# MainHubPCB.net
KiCad netlist of a schematic drawn in EAGLE
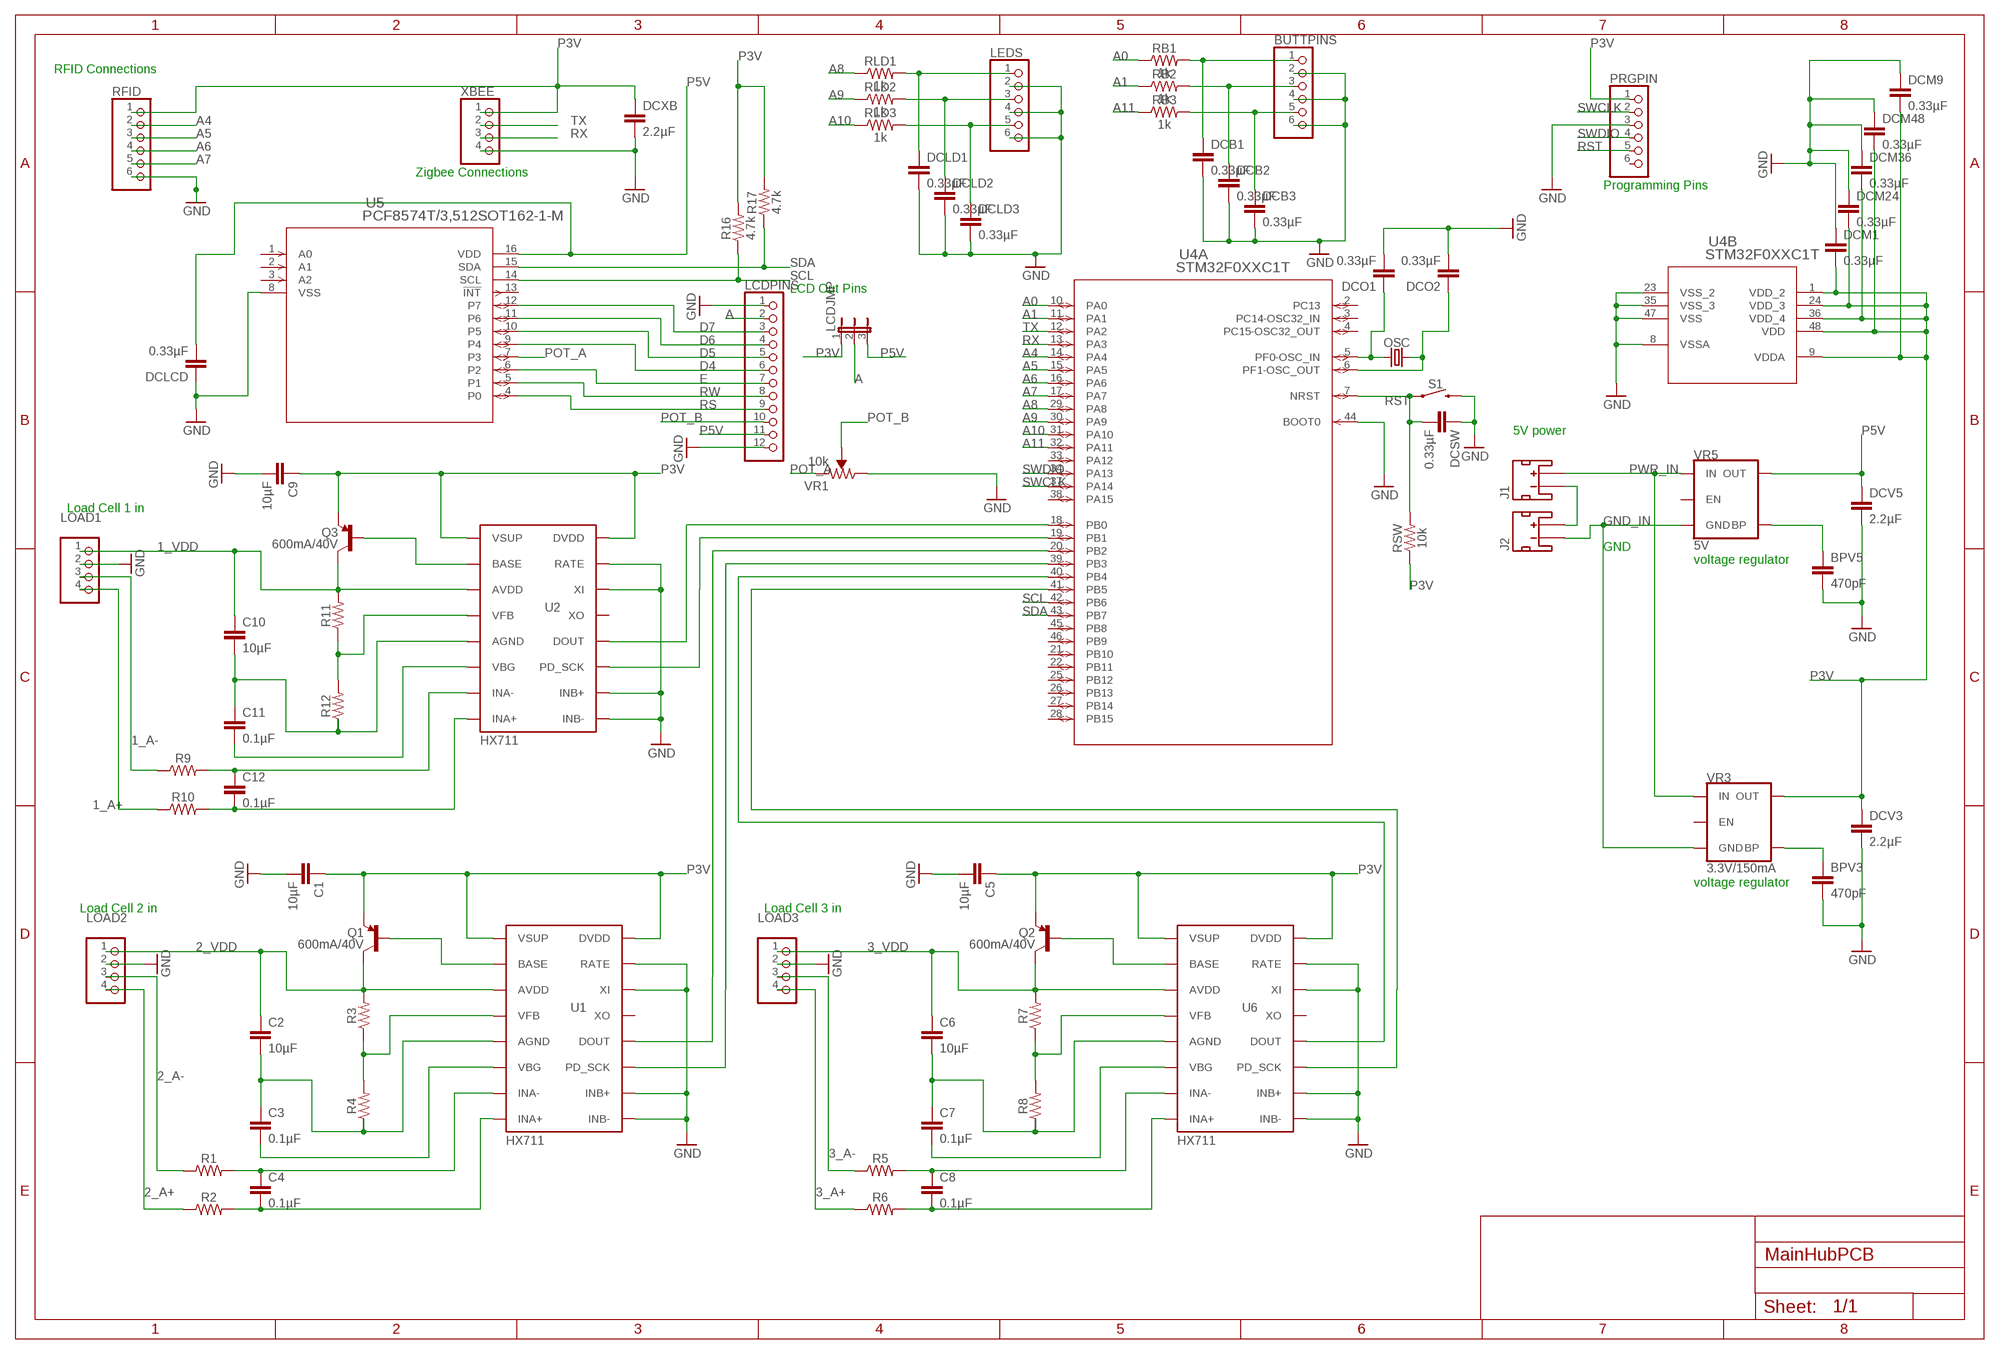
[diagram p0: schematic, sheet 1]

(export (version "E")
  (design (tool "Eeschema 10.0.6"))
  (components
    (comp (ref "BPV3")
      (value "470pF")
      (footprint "eagle-import:0805")
      (libsource (lib "eagle-import") (part "0.33UF/330NF-0805-50V-10%"))
    )
    (comp (ref "BPV5")
      (value "470pF")
      (footprint "eagle-import:0805")
      (libsource (lib "eagle-import") (part "0.33UF/330NF-0805-50V-10%"))
    )
    (comp (ref "BUTTPINS")
      (value "PINHD-1X6")
      (footprint "eagle-import:1X06")
      (libsource (lib "eagle-import") (part "PINHD-1X6"))
    )
    (comp (ref "C1")
      (value "10µF")
      (footprint "eagle-import:0805")
      (libsource (lib "eagle-import") (part "0.33UF/330NF-0805-50V-10%"))
    )
    (comp (ref "C2")
      (value "10µF")
      (footprint "eagle-import:0805")
      (libsource (lib "eagle-import") (part "0.33UF/330NF-0805-50V-10%"))
    )
    (comp (ref "C3")
      (value "0.1µF")
      (footprint "eagle-import:0805")
      (libsource (lib "eagle-import") (part "0.33UF/330NF-0805-50V-10%"))
    )
    (comp (ref "C4")
      (value "0.1µF")
      (footprint "eagle-import:0805")
      (libsource (lib "eagle-import") (part "0.33UF/330NF-0805-50V-10%"))
    )
    (comp (ref "C5")
      (value "10µF")
      (footprint "eagle-import:0805")
      (libsource (lib "eagle-import") (part "0.33UF/330NF-0805-50V-10%"))
    )
    (comp (ref "C6")
      (value "10µF")
      (footprint "eagle-import:0805")
      (libsource (lib "eagle-import") (part "0.33UF/330NF-0805-50V-10%"))
    )
    (comp (ref "C7")
      (value "0.1µF")
      (footprint "eagle-import:0805")
      (libsource (lib "eagle-import") (part "0.33UF/330NF-0805-50V-10%"))
    )
    (comp (ref "C8")
      (value "0.1µF")
      (footprint "eagle-import:0805")
      (libsource (lib "eagle-import") (part "0.33UF/330NF-0805-50V-10%"))
    )
    (comp (ref "C9")
      (value "10µF")
      (footprint "eagle-import:0805")
      (libsource (lib "eagle-import") (part "0.33UF/330NF-0805-50V-10%"))
    )
    (comp (ref "C10")
      (value "10µF")
      (footprint "eagle-import:0805")
      (libsource (lib "eagle-import") (part "0.33UF/330NF-0805-50V-10%"))
    )
    (comp (ref "C11")
      (value "0.1µF")
      (footprint "eagle-import:0805")
      (libsource (lib "eagle-import") (part "0.33UF/330NF-0805-50V-10%"))
    )
    (comp (ref "C12")
      (value "0.1µF")
      (footprint "eagle-import:0805")
      (libsource (lib "eagle-import") (part "0.33UF/330NF-0805-50V-10%"))
    )
    (comp (ref "DCB1")
      (value "0.33µF")
      (footprint "eagle-import:0805")
      (libsource (lib "eagle-import") (part "0.33UF/330NF-0805-50V-10%"))
    )
    (comp (ref "DCB2")
      (value "0.33µF")
      (footprint "eagle-import:0805")
      (libsource (lib "eagle-import") (part "0.33UF/330NF-0805-50V-10%"))
    )
    (comp (ref "DCB3")
      (value "0.33µF")
      (footprint "eagle-import:0805")
      (libsource (lib "eagle-import") (part "0.33UF/330NF-0805-50V-10%"))
    )
    (comp (ref "DCLCD")
      (value "0.33µF")
      (footprint "eagle-import:0805")
      (libsource (lib "eagle-import") (part "0.33UF/330NF-0805-50V-10%"))
    )
    (comp (ref "DCLD1")
      (value "0.33µF")
      (footprint "eagle-import:0805")
      (libsource (lib "eagle-import") (part "0.33UF/330NF-0805-50V-10%"))
    )
    (comp (ref "DCLD2")
      (value "0.33µF")
      (footprint "eagle-import:0805")
      (libsource (lib "eagle-import") (part "0.33UF/330NF-0805-50V-10%"))
    )
    (comp (ref "DCLD3")
      (value "0.33µF")
      (footprint "eagle-import:0805")
      (libsource (lib "eagle-import") (part "0.33UF/330NF-0805-50V-10%"))
    )
    (comp (ref "DCM1")
      (value "0.33µF")
      (footprint "eagle-import:0805")
      (libsource (lib "eagle-import") (part "0.33UF/330NF-0805-50V-10%"))
    )
    (comp (ref "DCM9")
      (value "0.33µF")
      (footprint "eagle-import:0805")
      (libsource (lib "eagle-import") (part "0.33UF/330NF-0805-50V-10%"))
    )
    (comp (ref "DCM24")
      (value "0.33µF")
      (footprint "eagle-import:0805")
      (libsource (lib "eagle-import") (part "0.33UF/330NF-0805-50V-10%"))
    )
    (comp (ref "DCM36")
      (value "0.33µF")
      (footprint "eagle-import:0805")
      (libsource (lib "eagle-import") (part "0.33UF/330NF-0805-50V-10%"))
    )
    (comp (ref "DCM48")
      (value "0.33µF")
      (footprint "eagle-import:0805")
      (libsource (lib "eagle-import") (part "0.33UF/330NF-0805-50V-10%"))
    )
    (comp (ref "DCO1")
      (value "0.33µF")
      (footprint "eagle-import:0805")
      (libsource (lib "eagle-import") (part "0.33UF/330NF-0805-50V-10%"))
    )
    (comp (ref "DCO2")
      (value "0.33µF")
      (footprint "eagle-import:0805")
      (libsource (lib "eagle-import") (part "0.33UF/330NF-0805-50V-10%"))
    )
    (comp (ref "DCSW")
      (value "0.33µF")
      (footprint "eagle-import:0805")
      (libsource (lib "eagle-import") (part "0.33UF/330NF-0805-50V-10%"))
    )
    (comp (ref "DCV3")
      (value "2.2µF")
      (footprint "eagle-import:0805")
      (libsource (lib "eagle-import") (part "0.33UF/330NF-0805-50V-10%"))
    )
    (comp (ref "DCV5")
      (value "2.2µF")
      (footprint "eagle-import:0805")
      (libsource (lib "eagle-import") (part "0.33UF/330NF-0805-50V-10%"))
    )
    (comp (ref "DCXB")
      (value "2.2µF")
      (footprint "eagle-import:0805")
      (libsource (lib "eagle-import") (part "0.33UF/330NF-0805-50V-10%"))
    )
    (comp (ref "J1")
      (value "JST_2MM_MALE")
      (footprint "eagle-import:JST-2-SMD")
      (libsource (lib "eagle-import") (part "JST_2MM_MALE"))
    )
    (comp (ref "J2")
      (value "JST_2MM_MALE")
      (footprint "eagle-import:JST-2-SMD")
      (libsource (lib "eagle-import") (part "JST_2MM_MALE"))
    )
    (comp (ref "LCDJMP")
      (value "JP2E")
      (footprint "eagle-import:JP2")
      (libsource (lib "eagle-import") (part "JP2E"))
    )
    (comp (ref "LCDPINS")
      (value "PINHD-1X12")
      (footprint "eagle-import:1X12")
      (libsource (lib "eagle-import") (part "PINHD-1X12"))
    )
    (comp (ref "LEDS")
      (value "PINHD-1X6")
      (footprint "eagle-import:1X06")
      (libsource (lib "eagle-import") (part "PINHD-1X6"))
    )
    (comp (ref "LOAD1")
      (value "PINHD-1X4")
      (footprint "eagle-import:1X04")
      (libsource (lib "eagle-import") (part "PINHD-1X4"))
    )
    (comp (ref "LOAD2")
      (value "PINHD-1X4")
      (footprint "eagle-import:1X04")
      (libsource (lib "eagle-import") (part "PINHD-1X4"))
    )
    (comp (ref "LOAD3")
      (value "PINHD-1X4")
      (footprint "eagle-import:1X04")
      (libsource (lib "eagle-import") (part "PINHD-1X4"))
    )
    (comp (ref "OSC")
      (value "CRYSTALPTH-HC49US")
      (footprint "eagle-import:HC49US")
      (libsource (lib "eagle-import") (part "CRYSTALPTH-HC49US"))
    )
    (comp (ref "PRGPIN")
      (value "PINHD-1X6")
      (footprint "eagle-import:1X06")
      (libsource (lib "eagle-import") (part "PINHD-1X6"))
    )
    (comp (ref "Q1")
      (value "600mA/40V")
      (footprint "eagle-import:SOT23-3")
      (libsource (lib "eagle-import") (part "TRANS_PNP-MMBT4403"))
    )
    (comp (ref "Q2")
      (value "600mA/40V")
      (footprint "eagle-import:SOT23-3")
      (libsource (lib "eagle-import") (part "TRANS_PNP-MMBT4403"))
    )
    (comp (ref "Q3")
      (value "600mA/40V")
      (footprint "eagle-import:SOT23-3")
      (libsource (lib "eagle-import") (part "TRANS_PNP-MMBT4403"))
    )
    (comp (ref "R1")
      (value "RESISTOR0805")
      (footprint "eagle-import:0805")
      (libsource (lib "eagle-import") (part "RESISTOR0805"))
    )
    (comp (ref "R2")
      (value "RESISTOR0805")
      (footprint "eagle-import:0805")
      (libsource (lib "eagle-import") (part "RESISTOR0805"))
    )
    (comp (ref "R3")
      (value "RESISTOR0805")
      (footprint "eagle-import:0805")
      (libsource (lib "eagle-import") (part "RESISTOR0805"))
    )
    (comp (ref "R4")
      (value "RESISTOR0805")
      (footprint "eagle-import:0805")
      (libsource (lib "eagle-import") (part "RESISTOR0805"))
    )
    (comp (ref "R5")
      (value "RESISTOR0805")
      (footprint "eagle-import:0805")
      (libsource (lib "eagle-import") (part "RESISTOR0805"))
    )
    (comp (ref "R6")
      (value "RESISTOR0805")
      (footprint "eagle-import:0805")
      (libsource (lib "eagle-import") (part "RESISTOR0805"))
    )
    (comp (ref "R7")
      (value "RESISTOR0805")
      (footprint "eagle-import:0805")
      (libsource (lib "eagle-import") (part "RESISTOR0805"))
    )
    (comp (ref "R8")
      (value "RESISTOR0805")
      (footprint "eagle-import:0805")
      (libsource (lib "eagle-import") (part "RESISTOR0805"))
    )
    (comp (ref "R9")
      (value "RESISTOR0805")
      (footprint "eagle-import:0805")
      (libsource (lib "eagle-import") (part "RESISTOR0805"))
    )
    (comp (ref "R10")
      (value "RESISTOR0805")
      (footprint "eagle-import:0805")
      (libsource (lib "eagle-import") (part "RESISTOR0805"))
    )
    (comp (ref "R11")
      (value "RESISTOR0805")
      (footprint "eagle-import:0805")
      (libsource (lib "eagle-import") (part "RESISTOR0805"))
    )
    (comp (ref "R12")
      (value "RESISTOR0805")
      (footprint "eagle-import:0805")
      (libsource (lib "eagle-import") (part "RESISTOR0805"))
    )
    (comp (ref "R16")
      (value "4.7k")
      (footprint "eagle-import:0805")
      (libsource (lib "eagle-import") (part "RESISTOR0805"))
    )
    (comp (ref "R17")
      (value "4.7k")
      (footprint "eagle-import:0805")
      (libsource (lib "eagle-import") (part "RESISTOR0805"))
    )
    (comp (ref "RB1")
      (value "1k")
      (footprint "eagle-import:0805")
      (libsource (lib "eagle-import") (part "RESISTOR0805"))
    )
    (comp (ref "RB2")
      (value "1k")
      (footprint "eagle-import:0805")
      (libsource (lib "eagle-import") (part "RESISTOR0805"))
    )
    (comp (ref "RB3")
      (value "1k")
      (footprint "eagle-import:0805")
      (libsource (lib "eagle-import") (part "RESISTOR0805"))
    )
    (comp (ref "RFID")
      (value "PINHD-1X6")
      (footprint "eagle-import:1X06")
      (libsource (lib "eagle-import") (part "PINHD-1X6"))
    )
    (comp (ref "RLD1")
      (value "1k")
      (footprint "eagle-import:0805")
      (libsource (lib "eagle-import") (part "RESISTOR0805"))
    )
    (comp (ref "RLD2")
      (value "1k")
      (footprint "eagle-import:0805")
      (libsource (lib "eagle-import") (part "RESISTOR0805"))
    )
    (comp (ref "RLD3")
      (value "1k")
      (footprint "eagle-import:0805")
      (libsource (lib "eagle-import") (part "RESISTOR0805"))
    )
    (comp (ref "RSW")
      (value "10k")
      (footprint "eagle-import:0805")
      (libsource (lib "eagle-import") (part "RESISTOR0805"))
    )
    (comp (ref "S1")
      (value "MOMENTARY-SWITCH-SPST-SMD-5.2MM")
      (footprint "eagle-import:TACTILE_SWITCH_SMD_5.2MM")
      (libsource (lib "eagle-import") (part "MOMENTARY-SWITCH-SPST-SMD-5.2MM"))
    )
    (comp (ref "U1")
      (value "HX711")
      (footprint "eagle-import:SO16")
      (libsource (lib "eagle-import") (part "HX711"))
    )
    (comp (ref "U2")
      (value "HX711")
      (footprint "eagle-import:SO16")
      (libsource (lib "eagle-import") (part "HX711"))
    )
    (comp (ref "U4")
      (value "STM32F0XXC1T")
      (footprint "eagle-import:LQFP48-7X7MM")
      (fields (field (name "MANUFACTURER_PART_NUMBER") "stm32f0xxc1t"))
      (libsource (lib "eagle-import") (part "STM32F0XXC1T"))
    )
    (comp (ref "U5")
      (value "PCF8574T/3,512SOT162-1-M")
      (footprint "eagle-import:SOT162-1-M")
      (fields (field (name "MANUFACTURER_PART_NUMBER") "PCF8574T3512"))
      (libsource (lib "eagle-import") (part "PCF8574T/3,512SOT162-1-M"))
    )
    (comp (ref "U6")
      (value "HX711")
      (footprint "eagle-import:SO16")
      (libsource (lib "eagle-import") (part "HX711"))
    )
    (comp (ref "VR1")
      (value "10k")
      (footprint "eagle-import:TRIMPOT-PTH-3386U")
      (libsource (lib "eagle-import") (part "TRIMPOT-PTH-10MM-KNOB-1/2W-10%"))
    )
    (comp (ref "VR3")
      (value "3.3V/150mA")
      (footprint "eagle-import:SOT23-5")
      (libsource (lib "eagle-import") (part "V_REG_MIC52053.3V"))
    )
    (comp (ref "VR5")
      (value "5V")
      (footprint "eagle-import:SOT23-5")
      (libsource (lib "eagle-import") (part "V_REG_MIC52055V"))
    )
    (comp (ref "XBEE")
      (value "PINHD-1X4")
      (footprint "eagle-import:1X04")
      (libsource (lib "eagle-import") (part "PINHD-1X4"))
    )
  )
  (nets
    (net (code "1") (name "/1_A+") (class "Default")
      (node (ref "LOAD1") (pin "4") (pinfunction "4_4") (pintype "passive"))
      (node (ref "R10") (pin "1") (pinfunction "1_1") (pintype "passive"))
    )
    (net (code "2") (name "/1_A-") (class "Default")
      (node (ref "LOAD1") (pin "3") (pinfunction "3_3") (pintype "passive"))
      (node (ref "R9") (pin "1") (pinfunction "1_1") (pintype "passive"))
    )
    (net (code "3") (name "/1_VDD") (class "Default")
      (node (ref "C10") (pin "1") (pinfunction "1_1") (pintype "passive"))
      (node (ref "LOAD1") (pin "1") (pinfunction "1_1") (pintype "passive"))
      (node (ref "Q3") (pin "3") (pinfunction "C_3") (pintype "passive"))
      (node (ref "R11") (pin "2") (pinfunction "2_2") (pintype "passive"))
      (node (ref "U2") (pin "3") (pinfunction "AVDD_3") (pintype "bidirectional"))
    )
    (net (code "4") (name "/2_A+") (class "Default")
      (node (ref "LOAD2") (pin "4") (pinfunction "4_4") (pintype "passive"))
      (node (ref "R2") (pin "1") (pinfunction "1_1") (pintype "passive"))
    )
    (net (code "5") (name "/2_A-") (class "Default")
      (node (ref "LOAD2") (pin "3") (pinfunction "3_3") (pintype "passive"))
      (node (ref "R1") (pin "1") (pinfunction "1_1") (pintype "passive"))
    )
    (net (code "6") (name "/2_VDD") (class "Default")
      (node (ref "C2") (pin "1") (pinfunction "1_1") (pintype "passive"))
      (node (ref "LOAD2") (pin "1") (pinfunction "1_1") (pintype "passive"))
      (node (ref "Q1") (pin "3") (pinfunction "C_3") (pintype "passive"))
      (node (ref "R3") (pin "2") (pinfunction "2_2") (pintype "passive"))
      (node (ref "U1") (pin "3") (pinfunction "AVDD_3") (pintype "bidirectional"))
    )
    (net (code "7") (name "/3_A+") (class "Default")
      (node (ref "LOAD3") (pin "4") (pinfunction "4_4") (pintype "passive"))
      (node (ref "R6") (pin "1") (pinfunction "1_1") (pintype "passive"))
    )
    (net (code "8") (name "/3_A-") (class "Default")
      (node (ref "LOAD3") (pin "3") (pinfunction "3_3") (pintype "passive"))
      (node (ref "R5") (pin "1") (pinfunction "1_1") (pintype "passive"))
    )
    (net (code "9") (name "/3_VDD") (class "Default")
      (node (ref "C6") (pin "1") (pinfunction "1_1") (pintype "passive"))
      (node (ref "LOAD3") (pin "1") (pinfunction "1_1") (pintype "passive"))
      (node (ref "Q2") (pin "3") (pinfunction "C_3") (pintype "passive"))
      (node (ref "R7") (pin "2") (pinfunction "2_2") (pintype "passive"))
      (node (ref "U6") (pin "3") (pinfunction "AVDD_3") (pintype "bidirectional"))
    )
    (net (code "10") (name "/A") (class "Default")
      (node (ref "LCDJMP") (pin "2") (pinfunction "2_2") (pintype "passive"))
      (node (ref "LCDPINS") (pin "2") (pinfunction "2_2") (pintype "passive"))
    )
    (net (code "11") (name "/A0") (class "Default")
      (node (ref "RB1") (pin "1") (pinfunction "1_1") (pintype "passive"))
      (node (ref "U4") (pin "10") (pinfunction "PA0_10") (pintype "bidirectional"))
    )
    (net (code "12") (name "/A1") (class "Default")
      (node (ref "RB2") (pin "1") (pinfunction "1_1") (pintype "passive"))
      (node (ref "U4") (pin "11") (pinfunction "PA1_11") (pintype "bidirectional"))
    )
    (net (code "13") (name "/A4") (class "Default")
      (node (ref "RFID") (pin "2") (pinfunction "2_2") (pintype "passive"))
      (node (ref "U4") (pin "14") (pinfunction "PA4_14") (pintype "bidirectional"))
    )
    (net (code "14") (name "/A5") (class "Default")
      (node (ref "RFID") (pin "3") (pinfunction "3_3") (pintype "passive"))
      (node (ref "U4") (pin "15") (pinfunction "PA5_15") (pintype "bidirectional"))
    )
    (net (code "15") (name "/A6") (class "Default")
      (node (ref "RFID") (pin "4") (pinfunction "4_4") (pintype "passive"))
      (node (ref "U4") (pin "16") (pinfunction "PA6_16") (pintype "bidirectional"))
    )
    (net (code "16") (name "/A7") (class "Default")
      (node (ref "RFID") (pin "5") (pinfunction "5_5") (pintype "passive"))
      (node (ref "U4") (pin "17") (pinfunction "PA7_17") (pintype "bidirectional"))
    )
    (net (code "17") (name "/A8") (class "Default")
      (node (ref "RLD1") (pin "1") (pinfunction "1_1") (pintype "passive"))
      (node (ref "U4") (pin "29") (pinfunction "PA8_29") (pintype "bidirectional"))
    )
    (net (code "18") (name "/A9") (class "Default")
      (node (ref "RLD2") (pin "1") (pinfunction "1_1") (pintype "passive"))
      (node (ref "U4") (pin "30") (pinfunction "PA9_30") (pintype "bidirectional"))
    )
    (net (code "19") (name "/A10") (class "Default")
      (node (ref "RLD3") (pin "1") (pinfunction "1_1") (pintype "passive"))
      (node (ref "U4") (pin "31") (pinfunction "PA10_31") (pintype "bidirectional"))
    )
    (net (code "20") (name "/A11") (class "Default")
      (node (ref "RB3") (pin "1") (pinfunction "1_1") (pintype "passive"))
      (node (ref "U4") (pin "32") (pinfunction "PA11_32") (pintype "bidirectional"))
    )
    (net (code "21") (name "/D4") (class "Default")
      (node (ref "LCDPINS") (pin "6") (pinfunction "6_6") (pintype "passive"))
      (node (ref "U5") (pin "9") (pinfunction "P4_9") (pintype "bidirectional"))
    )
    (net (code "22") (name "/D5") (class "Default")
      (node (ref "LCDPINS") (pin "5") (pinfunction "5_5") (pintype "passive"))
      (node (ref "U5") (pin "10") (pinfunction "P5_10") (pintype "bidirectional"))
    )
    (net (code "23") (name "/D6") (class "Default")
      (node (ref "LCDPINS") (pin "4") (pinfunction "4_4") (pintype "passive"))
      (node (ref "U5") (pin "11") (pinfunction "P6_11") (pintype "bidirectional"))
    )
    (net (code "24") (name "/D7") (class "Default")
      (node (ref "LCDPINS") (pin "3") (pinfunction "3_3") (pintype "passive"))
      (node (ref "U5") (pin "12") (pinfunction "P7_12") (pintype "bidirectional"))
    )
    (net (code "25") (name "/E") (class "Default")
      (node (ref "LCDPINS") (pin "7") (pinfunction "7_7") (pintype "passive"))
      (node (ref "U5") (pin "6") (pinfunction "P2_6") (pintype "bidirectional"))
    )
    (net (code "26") (name "/GND_IN") (class "Default")
      (node (ref "J2") (pin "1") (pinfunction "-_1") (pintype "bidirectional"))
      (node (ref "VR3") (pin "2") (pinfunction "GND_2") (pintype "input"))
      (node (ref "VR5") (pin "2") (pinfunction "GND_2") (pintype "input"))
    )
    (net (code "27") (name "/P3V") (class "Default")
      (node (ref "C1") (pin "1") (pinfunction "1_1") (pintype "passive"))
      (node (ref "C5") (pin "1") (pinfunction "1_1") (pintype "passive"))
      (node (ref "C9") (pin "1") (pinfunction "1_1") (pintype "passive"))
      (node (ref "DCM1") (pin "2") (pinfunction "2_2") (pintype "passive"))
      (node (ref "DCM24") (pin "2") (pinfunction "2_2") (pintype "passive"))
      (node (ref "DCM36") (pin "2") (pinfunction "2_2") (pintype "passive"))
      (node (ref "DCM48") (pin "2") (pinfunction "2_2") (pintype "passive"))
      (node (ref "DCM9") (pin "2") (pinfunction "2_2") (pintype "passive"))
      (node (ref "DCV3") (pin "1") (pinfunction "1_1") (pintype "passive"))
      (node (ref "DCXB") (pin "1") (pinfunction "1_1") (pintype "passive"))
      (node (ref "LCDJMP") (pin "1") (pinfunction "1_1") (pintype "passive"))
      (node (ref "PRGPIN") (pin "1") (pinfunction "1_1") (pintype "passive"))
      (node (ref "Q1") (pin "2") (pinfunction "E_2") (pintype "passive"))
      (node (ref "Q2") (pin "2") (pinfunction "E_2") (pintype "passive"))
      (node (ref "Q3") (pin "2") (pinfunction "E_2") (pintype "passive"))
      (node (ref "R16") (pin "2") (pinfunction "2_2") (pintype "passive"))
      (node (ref "R17") (pin "2") (pinfunction "2_2") (pintype "passive"))
      (node (ref "RFID") (pin "1") (pinfunction "1_1") (pintype "passive"))
      (node (ref "RSW") (pin "1") (pinfunction "1_1") (pintype "passive"))
      (node (ref "U1") (pin "1") (pinfunction "VSUP_1") (pintype "bidirectional"))
      (node (ref "U1") (pin "16") (pinfunction "DVDD_16") (pintype "bidirectional"))
      (node (ref "U2") (pin "1") (pinfunction "VSUP_1") (pintype "bidirectional"))
      (node (ref "U2") (pin "16") (pinfunction "DVDD_16") (pintype "bidirectional"))
      (node (ref "U4") (pin "1") (pinfunction "VDD_2_1") (pintype "power_in"))
      (node (ref "U4") (pin "24") (pinfunction "VDD_3_24") (pintype "power_in"))
      (node (ref "U4") (pin "36") (pinfunction "VDD_4_36") (pintype "power_in"))
      (node (ref "U4") (pin "48") (pinfunction "VDD_48") (pintype "power_in"))
      (node (ref "U4") (pin "9") (pinfunction "VDDA_9") (pintype "power_in"))
      (node (ref "U6") (pin "1") (pinfunction "VSUP_1") (pintype "bidirectional"))
      (node (ref "U6") (pin "16") (pinfunction "DVDD_16") (pintype "bidirectional"))
      (node (ref "VR3") (pin "5") (pinfunction "OUT_5") (pintype "passive"))
      (node (ref "XBEE") (pin "1") (pinfunction "1_1") (pintype "passive"))
    )
    (net (code "28") (name "/P5V") (class "Default")
      (node (ref "DCLCD") (pin "2") (pinfunction "2_2") (pintype "passive"))
      (node (ref "DCV5") (pin "1") (pinfunction "1_1") (pintype "passive"))
      (node (ref "LCDJMP") (pin "3") (pinfunction "3_3") (pintype "passive"))
      (node (ref "LCDPINS") (pin "11") (pinfunction "11_11") (pintype "passive"))
      (node (ref "U5") (pin "16") (pinfunction "VDD_16") (pintype "power_in"))
      (node (ref "VR5") (pin "5") (pinfunction "OUT_5") (pintype "passive"))
    )
    (net (code "29") (name "/POT_A") (class "Default")
      (node (ref "U5") (pin "7") (pinfunction "P3_7") (pintype "bidirectional"))
      (node (ref "VR1") (pin "1") (pinfunction "CCW_1") (pintype "passive"))
    )
    (net (code "30") (name "/POT_B") (class "Default")
      (node (ref "LCDPINS") (pin "10") (pinfunction "10_10") (pintype "passive"))
      (node (ref "VR1") (pin "2") (pinfunction "WIPER_2") (pintype "passive"))
    )
    (net (code "31") (name "/PWR_IN") (class "Default")
      (node (ref "J1") (pin "2") (pinfunction "+_2") (pintype "bidirectional"))
      (node (ref "VR3") (pin "1") (pinfunction "IN_1") (pintype "input"))
      (node (ref "VR5") (pin "1") (pinfunction "IN_1") (pintype "input"))
    )
    (net (code "32") (name "/RS") (class "Default")
      (node (ref "LCDPINS") (pin "9") (pinfunction "9_9") (pintype "passive"))
      (node (ref "U5") (pin "4") (pinfunction "P0_4") (pintype "bidirectional"))
    )
    (net (code "33") (name "/RST") (class "Default")
      (node (ref "DCSW") (pin "2") (pinfunction "2_2") (pintype "passive"))
      (node (ref "PRGPIN") (pin "5") (pinfunction "5_5") (pintype "passive"))
      (node (ref "RSW") (pin "2") (pinfunction "2_2") (pintype "passive"))
      (node (ref "S1") (pin "1") (pinfunction "1_1") (pintype "passive"))
      (node (ref "U4") (pin "7") (pinfunction "NRST_7") (pintype "bidirectional"))
    )
    (net (code "34") (name "/RW") (class "Default")
      (node (ref "LCDPINS") (pin "8") (pinfunction "8_8") (pintype "passive"))
      (node (ref "U5") (pin "5") (pinfunction "P1_5") (pintype "bidirectional"))
    )
    (net (code "35") (name "/RX") (class "Default")
      (node (ref "U4") (pin "13") (pinfunction "PA3_13") (pintype "bidirectional"))
      (node (ref "XBEE") (pin "3") (pinfunction "3_3") (pintype "passive"))
    )
    (net (code "36") (name "/SCL") (class "Default")
      (node (ref "R16") (pin "1") (pinfunction "1_1") (pintype "passive"))
      (node (ref "U4") (pin "42") (pinfunction "PB6_42") (pintype "bidirectional"))
      (node (ref "U5") (pin "14") (pinfunction "SCL_14") (pintype "passive"))
    )
    (net (code "37") (name "/SDA") (class "Default")
      (node (ref "R17") (pin "1") (pinfunction "1_1") (pintype "passive"))
      (node (ref "U4") (pin "43") (pinfunction "PB7_43") (pintype "bidirectional"))
      (node (ref "U5") (pin "15") (pinfunction "SDA_15") (pintype "passive"))
    )
    (net (code "38") (name "/SWCLK") (class "Default")
      (node (ref "PRGPIN") (pin "2") (pinfunction "2_2") (pintype "passive"))
      (node (ref "U4") (pin "37") (pinfunction "PA14_37") (pintype "bidirectional"))
    )
    (net (code "39") (name "/SWDIO") (class "Default")
      (node (ref "PRGPIN") (pin "4") (pinfunction "4_4") (pintype "passive"))
      (node (ref "U4") (pin "34") (pinfunction "PA13_34") (pintype "bidirectional"))
    )
    (net (code "40") (name "/TX") (class "Default")
      (node (ref "U4") (pin "12") (pinfunction "PA2_12") (pintype "bidirectional"))
      (node (ref "XBEE") (pin "2") (pinfunction "2_2") (pintype "passive"))
    )
    (net (code "41") (name "GND") (class "Default")
      (node (ref "BPV3") (pin "2") (pinfunction "2_2") (pintype "passive"))
      (node (ref "BPV5") (pin "2") (pinfunction "2_2") (pintype "passive"))
      (node (ref "BUTTPINS") (pin "2") (pinfunction "2_2") (pintype "passive"))
      (node (ref "BUTTPINS") (pin "4") (pinfunction "4_4") (pintype "passive"))
      (node (ref "BUTTPINS") (pin "6") (pinfunction "6_6") (pintype "passive"))
      (node (ref "C1") (pin "2") (pinfunction "2_2") (pintype "passive"))
      (node (ref "C5") (pin "2") (pinfunction "2_2") (pintype "passive"))
      (node (ref "C9") (pin "2") (pinfunction "2_2") (pintype "passive"))
      (node (ref "DCB1") (pin "2") (pinfunction "2_2") (pintype "passive"))
      (node (ref "DCB2") (pin "2") (pinfunction "2_2") (pintype "passive"))
      (node (ref "DCB3") (pin "2") (pinfunction "2_2") (pintype "passive"))
      (node (ref "DCLCD") (pin "1") (pinfunction "1_1") (pintype "passive"))
      (node (ref "DCLD1") (pin "2") (pinfunction "2_2") (pintype "passive"))
      (node (ref "DCLD2") (pin "2") (pinfunction "2_2") (pintype "passive"))
      (node (ref "DCLD3") (pin "2") (pinfunction "2_2") (pintype "passive"))
      (node (ref "DCM1") (pin "1") (pinfunction "1_1") (pintype "passive"))
      (node (ref "DCM24") (pin "1") (pinfunction "1_1") (pintype "passive"))
      (node (ref "DCM36") (pin "1") (pinfunction "1_1") (pintype "passive"))
      (node (ref "DCM48") (pin "1") (pinfunction "1_1") (pintype "passive"))
      (node (ref "DCM9") (pin "1") (pinfunction "1_1") (pintype "passive"))
      (node (ref "DCO1") (pin "2") (pinfunction "2_2") (pintype "passive"))
      (node (ref "DCO2") (pin "2") (pinfunction "2_2") (pintype "passive"))
      (node (ref "DCSW") (pin "1") (pinfunction "1_1") (pintype "passive"))
      (node (ref "DCV3") (pin "2") (pinfunction "2_2") (pintype "passive"))
      (node (ref "DCV5") (pin "2") (pinfunction "2_2") (pintype "passive"))
      (node (ref "DCXB") (pin "2") (pinfunction "2_2") (pintype "passive"))
      (node (ref "LCDPINS") (pin "1") (pinfunction "1_1") (pintype "passive"))
      (node (ref "LCDPINS") (pin "12") (pinfunction "12_12") (pintype "passive"))
      (node (ref "LEDS") (pin "2") (pinfunction "2_2") (pintype "passive"))
      (node (ref "LEDS") (pin "4") (pinfunction "4_4") (pintype "passive"))
      (node (ref "LEDS") (pin "6") (pinfunction "6_6") (pintype "passive"))
      (node (ref "LOAD1") (pin "2") (pinfunction "2_2") (pintype "passive"))
      (node (ref "LOAD2") (pin "2") (pinfunction "2_2") (pintype "passive"))
      (node (ref "LOAD3") (pin "2") (pinfunction "2_2") (pintype "passive"))
      (node (ref "PRGPIN") (pin "3") (pinfunction "3_3") (pintype "passive"))
      (node (ref "RFID") (pin "6") (pinfunction "6_6") (pintype "passive"))
      (node (ref "S1") (pin "3") (pinfunction "2_3") (pintype "passive"))
      (node (ref "U1") (pin "10") (pinfunction "INB+_10") (pintype "bidirectional"))
      (node (ref "U1") (pin "14") (pinfunction "XI_14") (pintype "bidirectional"))
      (node (ref "U1") (pin "15") (pinfunction "RATE_15") (pintype "bidirectional"))
      (node (ref "U1") (pin "9") (pinfunction "INB-_9") (pintype "bidirectional"))
      (node (ref "U2") (pin "10") (pinfunction "INB+_10") (pintype "bidirectional"))
      (node (ref "U2") (pin "14") (pinfunction "XI_14") (pintype "bidirectional"))
      (node (ref "U2") (pin "15") (pinfunction "RATE_15") (pintype "bidirectional"))
      (node (ref "U2") (pin "9") (pinfunction "INB-_9") (pintype "bidirectional"))
      (node (ref "U4") (pin "23") (pinfunction "VSS_2_23") (pintype "power_in"))
      (node (ref "U4") (pin "35") (pinfunction "VSS_3_35") (pintype "power_in"))
      (node (ref "U4") (pin "44") (pinfunction "BOOT0_44") (pintype "input"))
      (node (ref "U4") (pin "47") (pinfunction "VSS_47") (pintype "power_in"))
      (node (ref "U4") (pin "8") (pinfunction "VSSA_8") (pintype "power_in"))
      (node (ref "U5") (pin "8") (pinfunction "VSS_8") (pintype "power_in"))
      (node (ref "U6") (pin "10") (pinfunction "INB+_10") (pintype "bidirectional"))
      (node (ref "U6") (pin "14") (pinfunction "XI_14") (pintype "bidirectional"))
      (node (ref "U6") (pin "15") (pinfunction "RATE_15") (pintype "bidirectional"))
      (node (ref "U6") (pin "9") (pinfunction "INB-_9") (pintype "bidirectional"))
      (node (ref "VR1") (pin "3") (pinfunction "CW_3") (pintype "passive"))
      (node (ref "XBEE") (pin "4") (pinfunction "4_4") (pintype "passive"))
    )
    (net (code "42") (name "Net-(BUTTPINS-Pad1)") (class "Default")
      (node (ref "BUTTPINS") (pin "1") (pinfunction "1_1") (pintype "passive"))
      (node (ref "DCB1") (pin "1") (pinfunction "1_1") (pintype "passive"))
      (node (ref "RB1") (pin "2") (pinfunction "2_2") (pintype "passive"))
    )
    (net (code "43") (name "Net-(BUTTPINS-Pad3)") (class "Default")
      (node (ref "BUTTPINS") (pin "3") (pinfunction "3_3") (pintype "passive"))
      (node (ref "DCB2") (pin "1") (pinfunction "1_1") (pintype "passive"))
      (node (ref "RB2") (pin "2") (pinfunction "2_2") (pintype "passive"))
    )
    (net (code "44") (name "Net-(BUTTPINS-Pad5)") (class "Default")
      (node (ref "BUTTPINS") (pin "5") (pinfunction "5_5") (pintype "passive"))
      (node (ref "DCB3") (pin "1") (pinfunction "1_1") (pintype "passive"))
      (node (ref "RB3") (pin "2") (pinfunction "2_2") (pintype "passive"))
    )
    (net (code "45") (name "Net-(DCLD1-Pad1)") (class "Default")
      (node (ref "DCLD1") (pin "1") (pinfunction "1_1") (pintype "passive"))
      (node (ref "LEDS") (pin "1") (pinfunction "1_1") (pintype "passive"))
      (node (ref "RLD1") (pin "2") (pinfunction "2_2") (pintype "passive"))
    )
    (net (code "46") (name "Net-(DCLD2-Pad1)") (class "Default")
      (node (ref "DCLD2") (pin "1") (pinfunction "1_1") (pintype "passive"))
      (node (ref "LEDS") (pin "3") (pinfunction "3_3") (pintype "passive"))
      (node (ref "RLD2") (pin "2") (pinfunction "2_2") (pintype "passive"))
    )
    (net (code "47") (name "Net-(DCLD3-Pad1)") (class "Default")
      (node (ref "DCLD3") (pin "1") (pinfunction "1_1") (pintype "passive"))
      (node (ref "LEDS") (pin "5") (pinfunction "5_5") (pintype "passive"))
      (node (ref "RLD3") (pin "2") (pinfunction "2_2") (pintype "passive"))
    )
    (net (code "48") (name "Net-(J1--)") (class "Default")
      (node (ref "J1") (pin "1") (pinfunction "-_1") (pintype "bidirectional"))
      (node (ref "J2") (pin "2") (pinfunction "+_2") (pintype "bidirectional"))
    )
    (net (code "49") (name "Net-(Q1-B)") (class "Default")
      (node (ref "Q1") (pin "1") (pinfunction "B_1") (pintype "passive"))
      (node (ref "U1") (pin "2") (pinfunction "BASE_2") (pintype "bidirectional"))
    )
    (net (code "50") (name "Net-(Q2-B)") (class "Default")
      (node (ref "Q2") (pin "1") (pinfunction "B_1") (pintype "passive"))
      (node (ref "U6") (pin "2") (pinfunction "BASE_2") (pintype "bidirectional"))
    )
    (net (code "51") (name "Net-(Q3-B)") (class "Default")
      (node (ref "Q3") (pin "1") (pinfunction "B_1") (pintype "passive"))
      (node (ref "U2") (pin "2") (pinfunction "BASE_2") (pintype "bidirectional"))
    )
    (net (code "52") (name "Net-(U1-AGND)") (class "Default")
      (node (ref "C2") (pin "2") (pinfunction "2_2") (pintype "passive"))
      (node (ref "C3") (pin "1") (pinfunction "1_1") (pintype "passive"))
      (node (ref "R4") (pin "1") (pinfunction "1_1") (pintype "passive"))
      (node (ref "U1") (pin "5") (pinfunction "AGND_5") (pintype "bidirectional"))
    )
    (net (code "53") (name "Net-(U1-DOUT)") (class "Default")
      (node (ref "U1") (pin "12") (pinfunction "DOUT_12") (pintype "bidirectional"))
      (node (ref "U4") (pin "20") (pinfunction "PB2_20") (pintype "bidirectional"))
    )
    (net (code "54") (name "Net-(U1-INA+)") (class "Default")
      (node (ref "C4") (pin "2") (pinfunction "2_2") (pintype "passive"))
      (node (ref "R2") (pin "2") (pinfunction "2_2") (pintype "passive"))
      (node (ref "U1") (pin "8") (pinfunction "INA+_8") (pintype "bidirectional"))
    )
    (net (code "55") (name "Net-(U1-INA-)") (class "Default")
      (node (ref "C4") (pin "1") (pinfunction "1_1") (pintype "passive"))
      (node (ref "R1") (pin "2") (pinfunction "2_2") (pintype "passive"))
      (node (ref "U1") (pin "7") (pinfunction "INA-_7") (pintype "bidirectional"))
    )
    (net (code "56") (name "Net-(U1-PD_SCK)") (class "Default")
      (node (ref "U1") (pin "11") (pinfunction "PD_SCK_11") (pintype "bidirectional"))
      (node (ref "U4") (pin "39") (pinfunction "PB3_39") (pintype "bidirectional"))
    )
    (net (code "57") (name "Net-(U1-VBG)") (class "Default")
      (node (ref "C3") (pin "2") (pinfunction "2_2") (pintype "passive"))
      (node (ref "U1") (pin "6") (pinfunction "VBG_6") (pintype "bidirectional"))
    )
    (net (code "58") (name "Net-(U1-VFB)") (class "Default")
      (node (ref "R3") (pin "1") (pinfunction "1_1") (pintype "passive"))
      (node (ref "R4") (pin "2") (pinfunction "2_2") (pintype "passive"))
      (node (ref "U1") (pin "4") (pinfunction "VFB_4") (pintype "bidirectional"))
    )
    (net (code "59") (name "Net-(U2-AGND)") (class "Default")
      (node (ref "C10") (pin "2") (pinfunction "2_2") (pintype "passive"))
      (node (ref "C11") (pin "1") (pinfunction "1_1") (pintype "passive"))
      (node (ref "R12") (pin "1") (pinfunction "1_1") (pintype "passive"))
      (node (ref "U2") (pin "5") (pinfunction "AGND_5") (pintype "bidirectional"))
    )
    (net (code "60") (name "Net-(U2-DOUT)") (class "Default")
      (node (ref "U2") (pin "12") (pinfunction "DOUT_12") (pintype "bidirectional"))
      (node (ref "U4") (pin "18") (pinfunction "PB0_18") (pintype "bidirectional"))
    )
    (net (code "61") (name "Net-(U2-INA+)") (class "Default")
      (node (ref "C12") (pin "2") (pinfunction "2_2") (pintype "passive"))
      (node (ref "R10") (pin "2") (pinfunction "2_2") (pintype "passive"))
      (node (ref "U2") (pin "8") (pinfunction "INA+_8") (pintype "bidirectional"))
    )
    (net (code "62") (name "Net-(U2-INA-)") (class "Default")
      (node (ref "C12") (pin "1") (pinfunction "1_1") (pintype "passive"))
      (node (ref "R9") (pin "2") (pinfunction "2_2") (pintype "passive"))
      (node (ref "U2") (pin "7") (pinfunction "INA-_7") (pintype "bidirectional"))
    )
    (net (code "63") (name "Net-(U2-PD_SCK)") (class "Default")
      (node (ref "U2") (pin "11") (pinfunction "PD_SCK_11") (pintype "bidirectional"))
      (node (ref "U4") (pin "19") (pinfunction "PB1_19") (pintype "bidirectional"))
    )
    (net (code "64") (name "Net-(U2-VBG)") (class "Default")
      (node (ref "C11") (pin "2") (pinfunction "2_2") (pintype "passive"))
      (node (ref "U2") (pin "6") (pinfunction "VBG_6") (pintype "bidirectional"))
    )
    (net (code "65") (name "Net-(U2-VFB)") (class "Default")
      (node (ref "R11") (pin "1") (pinfunction "1_1") (pintype "passive"))
      (node (ref "R12") (pin "2") (pinfunction "2_2") (pintype "passive"))
      (node (ref "U2") (pin "4") (pinfunction "VFB_4") (pintype "bidirectional"))
    )
    (net (code "66") (name "Net-(U4A-PB4)") (class "Default")
      (node (ref "U4") (pin "40") (pinfunction "PB4_40") (pintype "bidirectional"))
      (node (ref "U6") (pin "12") (pinfunction "DOUT_12") (pintype "bidirectional"))
    )
    (net (code "67") (name "Net-(U4A-PB5)") (class "Default")
      (node (ref "U4") (pin "41") (pinfunction "PB5_41") (pintype "bidirectional"))
      (node (ref "U6") (pin "11") (pinfunction "PD_SCK_11") (pintype "bidirectional"))
    )
    (net (code "68") (name "Net-(U4A-PF0-OSC_IN)") (class "Default")
      (node (ref "DCO1") (pin "1") (pinfunction "1_1") (pintype "passive"))
      (node (ref "OSC") (pin "1") (pinfunction "1_1") (pintype "passive"))
      (node (ref "U4") (pin "5") (pinfunction "PF0-OSC_IN_5") (pintype "bidirectional"))
    )
    (net (code "69") (name "Net-(U4A-PF1-OSC_OUT)") (class "Default")
      (node (ref "DCO2") (pin "1") (pinfunction "1_1") (pintype "passive"))
      (node (ref "OSC") (pin "2") (pinfunction "2_2") (pintype "passive"))
      (node (ref "U4") (pin "6") (pinfunction "PF1-OSC_OUT_6") (pintype "bidirectional"))
    )
    (net (code "70") (name "Net-(U6-AGND)") (class "Default")
      (node (ref "C6") (pin "2") (pinfunction "2_2") (pintype "passive"))
      (node (ref "C7") (pin "1") (pinfunction "1_1") (pintype "passive"))
      (node (ref "R8") (pin "1") (pinfunction "1_1") (pintype "passive"))
      (node (ref "U6") (pin "5") (pinfunction "AGND_5") (pintype "bidirectional"))
    )
    (net (code "71") (name "Net-(U6-INA+)") (class "Default")
      (node (ref "C8") (pin "2") (pinfunction "2_2") (pintype "passive"))
      (node (ref "R6") (pin "2") (pinfunction "2_2") (pintype "passive"))
      (node (ref "U6") (pin "8") (pinfunction "INA+_8") (pintype "bidirectional"))
    )
    (net (code "72") (name "Net-(U6-INA-)") (class "Default")
      (node (ref "C8") (pin "1") (pinfunction "1_1") (pintype "passive"))
      (node (ref "R5") (pin "2") (pinfunction "2_2") (pintype "passive"))
      (node (ref "U6") (pin "7") (pinfunction "INA-_7") (pintype "bidirectional"))
    )
    (net (code "73") (name "Net-(U6-VBG)") (class "Default")
      (node (ref "C7") (pin "2") (pinfunction "2_2") (pintype "passive"))
      (node (ref "U6") (pin "6") (pinfunction "VBG_6") (pintype "bidirectional"))
    )
    (net (code "74") (name "Net-(U6-VFB)") (class "Default")
      (node (ref "R7") (pin "1") (pinfunction "1_1") (pintype "passive"))
      (node (ref "R8") (pin "2") (pinfunction "2_2") (pintype "passive"))
      (node (ref "U6") (pin "4") (pinfunction "VFB_4") (pintype "bidirectional"))
    )
    (net (code "75") (name "Net-(VR3-BP)") (class "Default")
      (node (ref "BPV3") (pin "1") (pinfunction "1_1") (pintype "passive"))
      (node (ref "VR3") (pin "4") (pinfunction "BP_4") (pintype "input"))
    )
    (net (code "76") (name "Net-(VR5-BP)") (class "Default")
      (node (ref "BPV5") (pin "1") (pinfunction "1_1") (pintype "passive"))
      (node (ref "VR5") (pin "4") (pinfunction "BP_4") (pintype "input"))
    )
    (net (code "77") (name "unconnected-(J1-PAD1-PadNC1)") (class "Default")
      (node (ref "J1") (pin "NC1") (pinfunction "PAD1_NC1") (pintype "bidirectional"))
    )
    (net (code "78") (name "unconnected-(J1-PAD2-PadNC2)") (class "Default")
      (node (ref "J1") (pin "NC2") (pinfunction "PAD2_NC2") (pintype "bidirectional"))
    )
    (net (code "79") (name "unconnected-(J2-PAD1-PadNC1)") (class "Default")
      (node (ref "J2") (pin "NC1") (pinfunction "PAD1_NC1") (pintype "bidirectional"))
    )
    (net (code "80") (name "unconnected-(J2-PAD2-PadNC2)") (class "Default")
      (node (ref "J2") (pin "NC2") (pinfunction "PAD2_NC2") (pintype "bidirectional"))
    )
    (net (code "81") (name "unconnected-(PRGPIN-Pad6)") (class "Default")
      (node (ref "PRGPIN") (pin "6") (pinfunction "6_6") (pintype "passive"))
    )
    (net (code "82") (name "unconnected-(U1-XO-Pad13)") (class "Default")
      (node (ref "U1") (pin "13") (pinfunction "XO_13") (pintype "bidirectional"))
    )
    (net (code "83") (name "unconnected-(U2-XO-Pad13)") (class "Default")
      (node (ref "U2") (pin "13") (pinfunction "XO_13") (pintype "bidirectional"))
    )
    (net (code "84") (name "unconnected-(U4A-PA12-Pad33)") (class "Default")
      (node (ref "U4") (pin "33") (pinfunction "PA12_33") (pintype "bidirectional"))
    )
    (net (code "85") (name "unconnected-(U4A-PA15-Pad38)") (class "Default")
      (node (ref "U4") (pin "38") (pinfunction "PA15_38") (pintype "bidirectional"))
    )
    (net (code "86") (name "unconnected-(U4A-PB8-Pad45)") (class "Default")
      (node (ref "U4") (pin "45") (pinfunction "PB8_45") (pintype "bidirectional"))
    )
    (net (code "87") (name "unconnected-(U4A-PB9-Pad46)") (class "Default")
      (node (ref "U4") (pin "46") (pinfunction "PB9_46") (pintype "bidirectional"))
    )
    (net (code "88") (name "unconnected-(U4A-PB10-Pad21)") (class "Default")
      (node (ref "U4") (pin "21") (pinfunction "PB10_21") (pintype "bidirectional"))
    )
    (net (code "89") (name "unconnected-(U4A-PB11-Pad22)") (class "Default")
      (node (ref "U4") (pin "22") (pinfunction "PB11_22") (pintype "bidirectional"))
    )
    (net (code "90") (name "unconnected-(U4A-PB12-Pad25)") (class "Default")
      (node (ref "U4") (pin "25") (pinfunction "PB12_25") (pintype "bidirectional"))
    )
    (net (code "91") (name "unconnected-(U4A-PB13-Pad26)") (class "Default")
      (node (ref "U4") (pin "26") (pinfunction "PB13_26") (pintype "bidirectional"))
    )
    (net (code "92") (name "unconnected-(U4A-PB14-Pad27)") (class "Default")
      (node (ref "U4") (pin "27") (pinfunction "PB14_27") (pintype "bidirectional"))
    )
    (net (code "93") (name "unconnected-(U4A-PB15-Pad28)") (class "Default")
      (node (ref "U4") (pin "28") (pinfunction "PB15_28") (pintype "bidirectional"))
    )
    (net (code "94") (name "unconnected-(U4A-PC13-Pad2)") (class "Default")
      (node (ref "U4") (pin "2") (pinfunction "PC13_2") (pintype "bidirectional"))
    )
    (net (code "95") (name "unconnected-(U4A-PC14-OSC32_IN-Pad3)") (class "Default")
      (node (ref "U4") (pin "3") (pinfunction "PC14-OSC32_IN_3") (pintype "bidirectional"))
    )
    (net (code "96") (name "unconnected-(U4A-PC15-OSC32_OUT-Pad4)") (class "Default")
      (node (ref "U4") (pin "4") (pinfunction "PC15-OSC32_OUT_4") (pintype "bidirectional"))
    )
    (net (code "97") (name "unconnected-(U5-A0-Pad1)") (class "Default")
      (node (ref "U5") (pin "1") (pinfunction "A0_1") (pintype "input"))
    )
    (net (code "98") (name "unconnected-(U5-A1-Pad2)") (class "Default")
      (node (ref "U5") (pin "2") (pinfunction "A1_2") (pintype "input"))
    )
    (net (code "99") (name "unconnected-(U5-A2-Pad3)") (class "Default")
      (node (ref "U5") (pin "3") (pinfunction "A2_3") (pintype "input"))
    )
    (net (code "100") (name "unconnected-(U5-~{INT}-Pad13)") (class "Default")
      (node (ref "U5") (pin "13") (pinfunction "~{INT}_13") (pintype "output"))
    )
    (net (code "101") (name "unconnected-(U6-XO-Pad13)") (class "Default")
      (node (ref "U6") (pin "13") (pinfunction "XO_13") (pintype "bidirectional"))
    )
    (net (code "102") (name "unconnected-(VR3-EN-Pad3)") (class "Default")
      (node (ref "VR3") (pin "3") (pinfunction "EN_3") (pintype "input"))
    )
    (net (code "103") (name "unconnected-(VR5-EN-Pad3)") (class "Default")
      (node (ref "VR5") (pin "3") (pinfunction "EN_3") (pintype "input"))
    )
  )
)
